# poorDuino.net
KiCad netlist of a schematic drawn in EAGLE
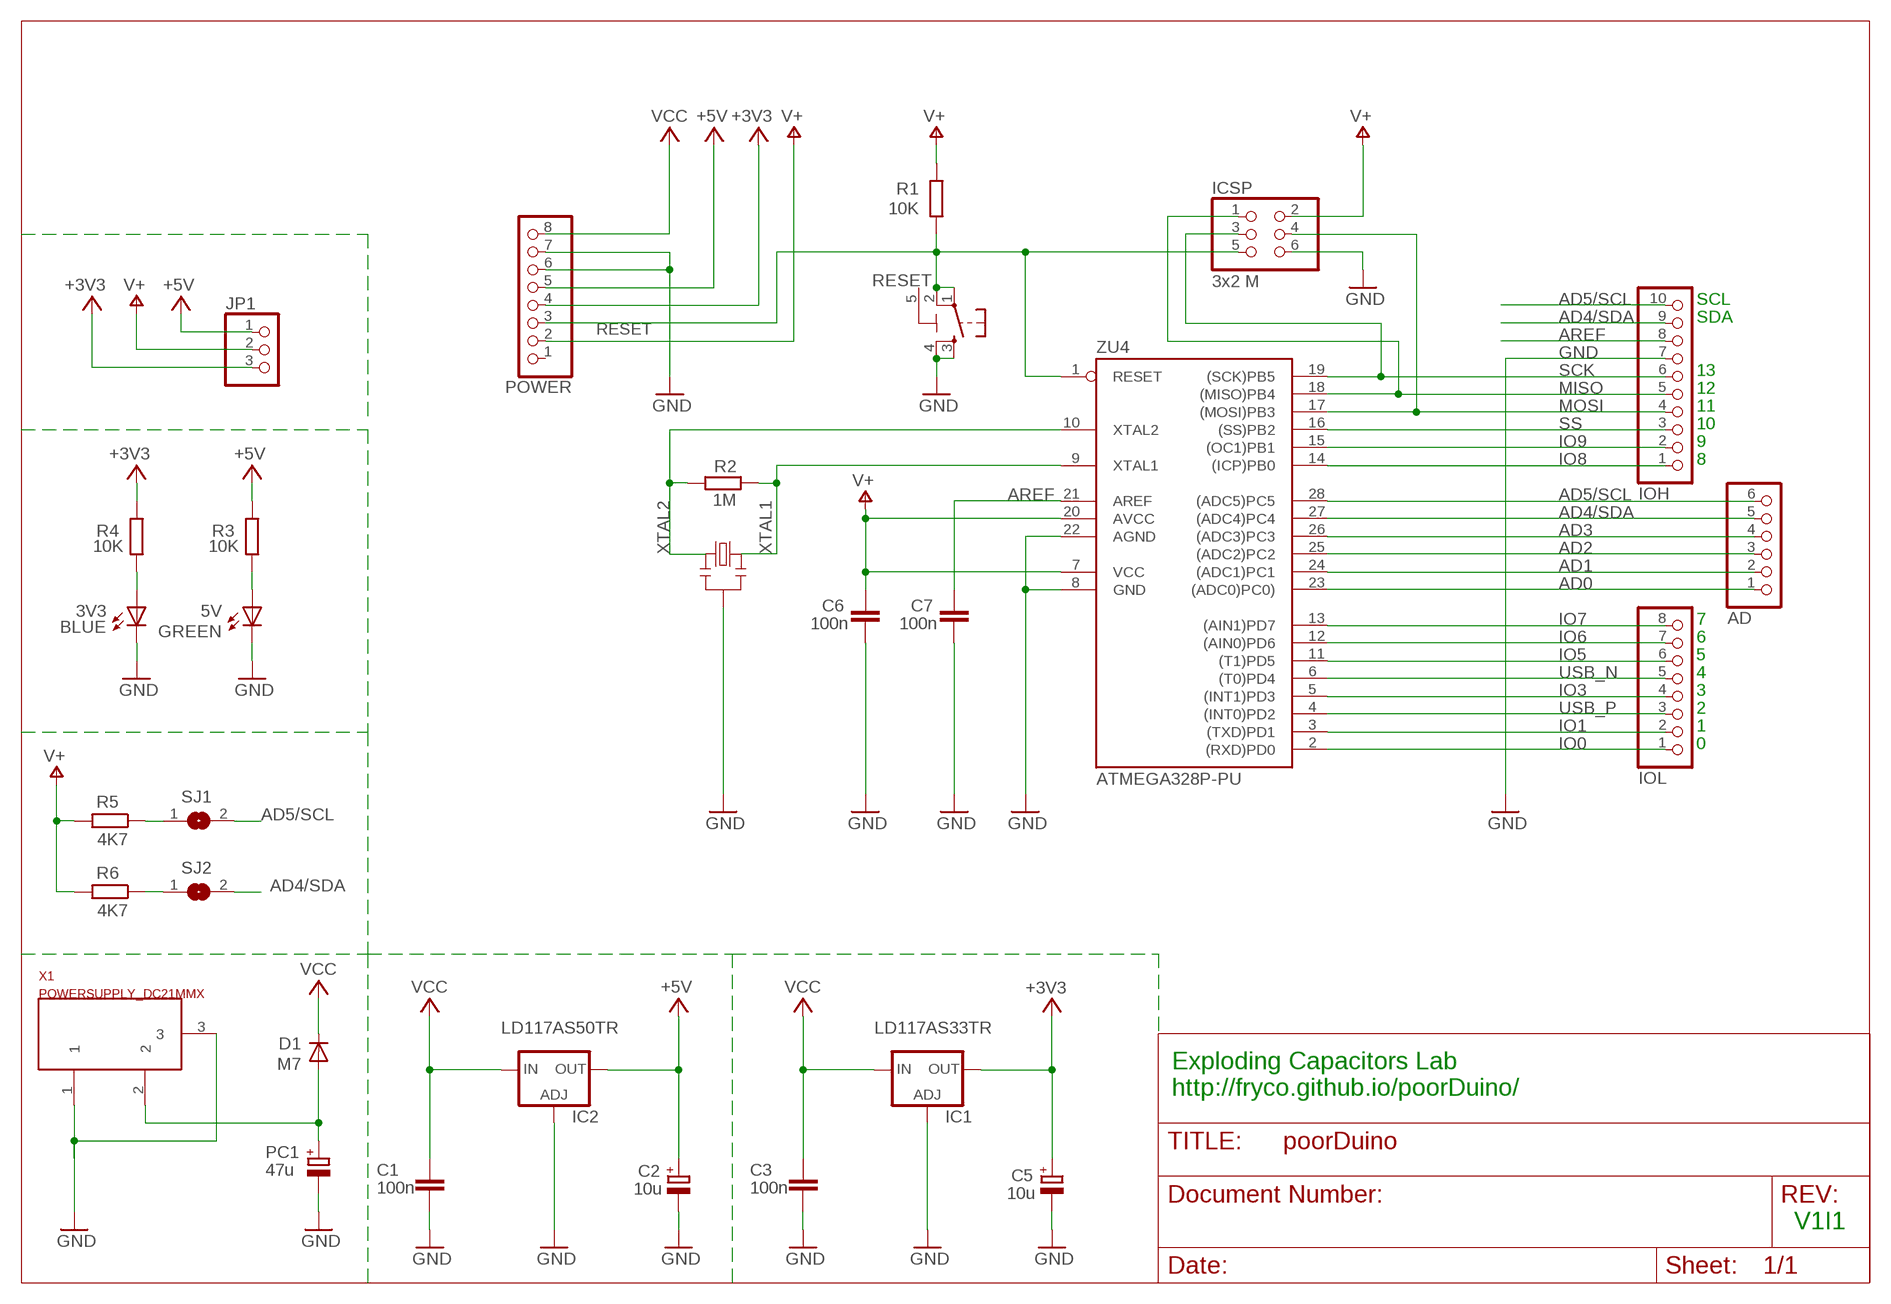
[diagram p0: schematic, sheet 1]

(export (version "E")
  (design (tool "Eeschema 10.0.6"))
  (components
    (comp (ref "3V3")
      (value "BLUE")
      (footprint "eagle-import:CHIP-LED0805")
      (libsource (lib "eagle-import") (part "LEDCHIP-LED0805"))
    )
    (comp (ref "5V")
      (value "GREEN")
      (footprint "eagle-import:CHIP-LED0805")
      (libsource (lib "eagle-import") (part "LEDCHIP-LED0805"))
    )
    (comp (ref "AD")
      (value "6x1F-H8.5")
      (footprint "eagle-import:1X06")
      (libsource (lib "eagle-import") (part "PINHD-1X6"))
    )
    (comp (ref "C1")
      (value "100n")
      (footprint "eagle-import:C0805")
      (libsource (lib "eagle-import") (part "C-EUC0805"))
    )
    (comp (ref "C2")
      (value "10u")
      (footprint "eagle-import:SMC_A")
      (libsource (lib "eagle-import") (part "CPOL-EUSMCA"))
    )
    (comp (ref "C3")
      (value "100n")
      (footprint "eagle-import:C0805")
      (libsource (lib "eagle-import") (part "C-EUC0805"))
    )
    (comp (ref "C5")
      (value "10u")
      (footprint "eagle-import:SMC_A")
      (libsource (lib "eagle-import") (part "CPOL-EUSMCA"))
    )
    (comp (ref "C6")
      (value "100n")
      (footprint "eagle-import:C0805")
      (libsource (lib "eagle-import") (part "C-EUC0805"))
    )
    (comp (ref "C7")
      (value "100n")
      (footprint "eagle-import:C0805")
      (libsource (lib "eagle-import") (part "C-EUC0805"))
    )
    (comp (ref "D1")
      (value "M7")
      (footprint "eagle-import:SMB")
      (libsource (lib "eagle-import") (part "DIODE-SMB"))
    )
    (comp (ref "IC1")
      (value "LD117AS33TR")
      (footprint "eagle-import:SOT223")
      (libsource (lib "eagle-import") (part "LD117A?S33TR"))
    )
    (comp (ref "IC2")
      (value "LD117AS50TR")
      (footprint "eagle-import:SOT223")
      (libsource (lib "eagle-import") (part "LD117A?S50TR"))
    )
    (comp (ref "ICSP")
      (value "3x2 M")
      (footprint "eagle-import:2X03")
      (libsource (lib "eagle-import") (part "PINHD-2X3"))
    )
    (comp (ref "IOH")
      (value "10x1F-H8.5")
      (footprint "eagle-import:1X10")
      (libsource (lib "eagle-import") (part "PINHD-1X10_ARD"))
    )
    (comp (ref "IOL")
      (value "8x1F-H8.5")
      (footprint "eagle-import:1X08")
      (libsource (lib "eagle-import") (part "PINHD-1X8"))
    )
    (comp (ref "JP1")
      (value "PINHD-1X3")
      (footprint "eagle-import:1X03")
      (libsource (lib "eagle-import") (part "PINHD-1X3"))
    )
    (comp (ref "PC1")
      (value "47u")
      (footprint "eagle-import:PANASONIC_D")
      (libsource (lib "eagle-import") (part "CPOL-EUD"))
    )
    (comp (ref "POWER")
      (value "8x1F-H8.5")
      (footprint "eagle-import:1X08")
      (libsource (lib "eagle-import") (part "PINHD-1X8"))
    )
    (comp (ref "R1")
      (value "10K")
      (footprint "eagle-import:R0805")
      (libsource (lib "eagle-import") (part "R-EU_R0805"))
    )
    (comp (ref "R2")
      (value "1M")
      (footprint "eagle-import:R0805")
      (libsource (lib "eagle-import") (part "R-EU_R0805"))
    )
    (comp (ref "R3")
      (value "10K")
      (footprint "eagle-import:R0805")
      (libsource (lib "eagle-import") (part "R-EU_R0805"))
    )
    (comp (ref "R4")
      (value "10K")
      (footprint "eagle-import:R0805")
      (libsource (lib "eagle-import") (part "R-EU_R0805"))
    )
    (comp (ref "R5")
      (value "4K7")
      (footprint "eagle-import:R0805")
      (libsource (lib "eagle-import") (part "R-EU_R0805"))
    )
    (comp (ref "R6")
      (value "4K7")
      (footprint "eagle-import:R0805")
      (libsource (lib "eagle-import") (part "R-EU_R0805"))
    )
    (comp (ref "RESET")
      (value "TS42031-160R-TR-7260")
      (footprint "eagle-import:TS42")
      (libsource (lib "eagle-import") (part "TS42"))
    )
    (comp (ref "SJ1") (value "SJ") (footprint "eagle-import:SJ") (libsource (lib "eagle-import") (part "SJ")))
    (comp (ref "SJ2") (value "SJ") (footprint "eagle-import:SJ") (libsource (lib "eagle-import") (part "SJ")))
    (comp (ref "X1")
      (value "POWERSUPPLY_DC21MMX")
      (footprint "eagle-import:POWERSUPPLY_DC-21MM")
      (libsource (lib "eagle-import") (part "POWERSUPPLY_DC21MMX"))
    )
    (comp (ref "Y2")
      (value "CSTCE16M0V53-R0 16MHZ")
      (footprint "eagle-import:RESONATOR")
      (libsource (lib "eagle-import") (part "RESONATORMU"))
    )
    (comp (ref "ZU4")
      (value "ATMEGA328P-PU")
      (footprint "eagle-import:DIL28-3")
      (libsource (lib "eagle-import") (part "ATMEGA328P-PU"))
    )
  )
  (nets
    (net (code "1") (name "+3V3") (class "Default")
      (node (ref "C5") (pin "+") (pinfunction "+_+") (pintype "passive"))
      (node (ref "IC1") (pin "4") (pinfunction "OUT_4") (pintype "passive"))
      (node (ref "JP1") (pin "3") (pinfunction "3_3") (pintype "passive"))
      (node (ref "POWER") (pin "4") (pinfunction "4_4") (pintype "passive"))
      (node (ref "R4") (pin "1") (pinfunction "1_1") (pintype "passive"))
    )
    (net (code "2") (name "+5V") (class "Default")
      (node (ref "C2") (pin "+") (pinfunction "+_+") (pintype "passive"))
      (node (ref "IC2") (pin "4") (pinfunction "OUT_4") (pintype "passive"))
      (node (ref "JP1") (pin "1") (pinfunction "1_1") (pintype "passive"))
      (node (ref "POWER") (pin "5") (pinfunction "5_5") (pintype "passive"))
      (node (ref "R3") (pin "1") (pinfunction "1_1") (pintype "passive"))
    )
    (net (code "3") (name "/5-GND") (class "Default")
      (node (ref "RESET") (pin "5") (pinfunction "5-GND_5") (pintype "power_in"))
    )
    (net (code "4") (name "/AD0") (class "Default")
      (node (ref "AD") (pin "1") (pinfunction "1_1") (pintype "passive"))
      (node (ref "ZU4") (pin "23") (pinfunction "(ADC0)PC0)_23") (pintype "bidirectional"))
    )
    (net (code "5") (name "/AD1") (class "Default")
      (node (ref "AD") (pin "2") (pinfunction "2_2") (pintype "passive"))
      (node (ref "ZU4") (pin "24") (pinfunction "(ADC1)PC1_24") (pintype "bidirectional"))
    )
    (net (code "6") (name "/AD2") (class "Default")
      (node (ref "AD") (pin "3") (pinfunction "3_3") (pintype "passive"))
      (node (ref "ZU4") (pin "25") (pinfunction "(ADC2)PC2_25") (pintype "bidirectional"))
    )
    (net (code "7") (name "/AD3") (class "Default")
      (node (ref "AD") (pin "4") (pinfunction "4_4") (pintype "passive"))
      (node (ref "ZU4") (pin "26") (pinfunction "(ADC3)PC3_26") (pintype "bidirectional"))
    )
    (net (code "8") (name "/AD4{slash}SDA") (class "Default")
      (node (ref "AD") (pin "5") (pinfunction "5_5") (pintype "passive"))
      (node (ref "IOH") (pin "9") (pinfunction "9_9") (pintype "passive"))
      (node (ref "SJ2") (pin "2") (pinfunction "2_2") (pintype "passive"))
      (node (ref "ZU4") (pin "27") (pinfunction "(ADC4)PC4_27") (pintype "bidirectional"))
    )
    (net (code "9") (name "/AD5{slash}SCL") (class "Default")
      (node (ref "AD") (pin "6") (pinfunction "6_6") (pintype "passive"))
      (node (ref "IOH") (pin "10") (pinfunction "10_10") (pintype "passive"))
      (node (ref "SJ1") (pin "2") (pinfunction "2_2") (pintype "passive"))
      (node (ref "ZU4") (pin "28") (pinfunction "(ADC5)PC5_28") (pintype "bidirectional"))
    )
    (net (code "10") (name "/AREF") (class "Default")
      (node (ref "C7") (pin "2") (pinfunction "2_2") (pintype "passive"))
      (node (ref "IOH") (pin "8") (pinfunction "8_8") (pintype "passive"))
      (node (ref "ZU4") (pin "21") (pinfunction "AREF_21") (pintype "passive"))
    )
    (net (code "11") (name "/IO0") (class "Default")
      (node (ref "IOL") (pin "1") (pinfunction "1_1") (pintype "passive"))
      (node (ref "ZU4") (pin "2") (pinfunction "(RXD)PD0_2") (pintype "bidirectional"))
    )
    (net (code "12") (name "/IO1") (class "Default")
      (node (ref "IOL") (pin "2") (pinfunction "2_2") (pintype "passive"))
      (node (ref "ZU4") (pin "3") (pinfunction "(TXD)PD1_3") (pintype "bidirectional"))
    )
    (net (code "13") (name "/IO3") (class "Default")
      (node (ref "IOL") (pin "4") (pinfunction "4_4") (pintype "passive"))
      (node (ref "ZU4") (pin "5") (pinfunction "(INT1)PD3_5") (pintype "bidirectional"))
    )
    (net (code "14") (name "/IO5") (class "Default")
      (node (ref "IOL") (pin "6") (pinfunction "6_6") (pintype "passive"))
      (node (ref "ZU4") (pin "11") (pinfunction "(T1)PD5_11") (pintype "bidirectional"))
    )
    (net (code "15") (name "/IO6") (class "Default")
      (node (ref "IOL") (pin "7") (pinfunction "7_7") (pintype "passive"))
      (node (ref "ZU4") (pin "12") (pinfunction "(AIN0)PD6_12") (pintype "bidirectional"))
    )
    (net (code "16") (name "/IO7") (class "Default")
      (node (ref "IOL") (pin "8") (pinfunction "8_8") (pintype "passive"))
      (node (ref "ZU4") (pin "13") (pinfunction "(AIN1)PD7_13") (pintype "bidirectional"))
    )
    (net (code "17") (name "/IO8") (class "Default")
      (node (ref "IOH") (pin "1") (pinfunction "1_1") (pintype "passive"))
      (node (ref "ZU4") (pin "14") (pinfunction "(ICP)PB0_14") (pintype "bidirectional"))
    )
    (net (code "18") (name "/IO9") (class "Default")
      (node (ref "IOH") (pin "2") (pinfunction "2_2") (pintype "passive"))
      (node (ref "ZU4") (pin "15") (pinfunction "(OC1)PB1_15") (pintype "bidirectional"))
    )
    (net (code "19") (name "/MISO") (class "Default")
      (node (ref "ICSP") (pin "1") (pinfunction "1_1") (pintype "passive"))
      (node (ref "IOH") (pin "5") (pinfunction "5_5") (pintype "passive"))
      (node (ref "ZU4") (pin "18") (pinfunction "(MISO)PB4_18") (pintype "bidirectional"))
    )
    (net (code "20") (name "/MOSI") (class "Default")
      (node (ref "ICSP") (pin "4") (pinfunction "4_4") (pintype "passive"))
      (node (ref "IOH") (pin "4") (pinfunction "4_4") (pintype "passive"))
      (node (ref "ZU4") (pin "17") (pinfunction "(MOSI)PB3_17") (pintype "bidirectional"))
    )
    (net (code "22") (name "/RESET") (class "Default")
      (node (ref "ICSP") (pin "5") (pinfunction "5_5") (pintype "passive"))
      (node (ref "POWER") (pin "3") (pinfunction "3_3") (pintype "passive"))
      (node (ref "R1") (pin "1") (pinfunction "1_1") (pintype "passive"))
      (node (ref "RESET") (pin "1") (pinfunction "1_1") (pintype "passive"))
      (node (ref "RESET") (pin "2") (pinfunction "2_2") (pintype "passive"))
      (node (ref "ZU4") (pin "1") (pinfunction "RESET_1") (pintype "input"))
    )
    (net (code "23") (name "/SCK") (class "Default")
      (node (ref "ICSP") (pin "3") (pinfunction "3_3") (pintype "passive"))
      (node (ref "IOH") (pin "6") (pinfunction "6_6") (pintype "passive"))
      (node (ref "ZU4") (pin "19") (pinfunction "(SCK)PB5_19") (pintype "bidirectional"))
    )
    (net (code "24") (name "/SS") (class "Default")
      (node (ref "IOH") (pin "3") (pinfunction "3_3") (pintype "passive"))
      (node (ref "ZU4") (pin "16") (pinfunction "(SS)PB2_16") (pintype "bidirectional"))
    )
    (net (code "25") (name "/USB_N") (class "Default")
      (node (ref "IOL") (pin "5") (pinfunction "5_5") (pintype "passive"))
      (node (ref "ZU4") (pin "6") (pinfunction "(T0)PD4_6") (pintype "bidirectional"))
    )
    (net (code "26") (name "/USB_P") (class "Default")
      (node (ref "IOL") (pin "3") (pinfunction "3_3") (pintype "passive"))
      (node (ref "ZU4") (pin "4") (pinfunction "(INT0)PD2_4") (pintype "bidirectional"))
    )
    (net (code "27") (name "/XTAL1") (class "Default")
      (node (ref "R2") (pin "1") (pinfunction "1_1") (pintype "passive"))
      (node (ref "Y2") (pin "3") (pinfunction "3_3") (pintype "passive"))
      (node (ref "ZU4") (pin "9") (pinfunction "XTAL1_9") (pintype "bidirectional"))
    )
    (net (code "28") (name "/XTAL2") (class "Default")
      (node (ref "R2") (pin "2") (pinfunction "2_2") (pintype "passive"))
      (node (ref "Y2") (pin "1") (pinfunction "1_1") (pintype "passive"))
      (node (ref "ZU4") (pin "10") (pinfunction "XTAL2_10") (pintype "bidirectional"))
    )
    (net (code "29") (name "GND") (class "Default")
      (node (ref "3V3") (pin "C") (pinfunction "C_C") (pintype "passive"))
      (node (ref "5V") (pin "C") (pinfunction "C_C") (pintype "passive"))
      (node (ref "C1") (pin "1") (pinfunction "1_1") (pintype "passive"))
      (node (ref "C2") (pin "-") (pinfunction "-_-") (pintype "passive"))
      (node (ref "C3") (pin "1") (pinfunction "1_1") (pintype "passive"))
      (node (ref "C5") (pin "-") (pinfunction "-_-") (pintype "passive"))
      (node (ref "C6") (pin "1") (pinfunction "1_1") (pintype "passive"))
      (node (ref "C7") (pin "1") (pinfunction "1_1") (pintype "passive"))
      (node (ref "IC1") (pin "1") (pinfunction "ADJ_1") (pintype "input"))
      (node (ref "IC2") (pin "1") (pinfunction "ADJ_1") (pintype "input"))
      (node (ref "ICSP") (pin "6") (pinfunction "6_6") (pintype "passive"))
      (node (ref "IOH") (pin "7") (pinfunction "7_7") (pintype "passive"))
      (node (ref "PC1") (pin "-") (pinfunction "-_-") (pintype "passive"))
      (node (ref "POWER") (pin "6") (pinfunction "6_6") (pintype "passive"))
      (node (ref "POWER") (pin "7") (pinfunction "7_7") (pintype "passive"))
      (node (ref "RESET") (pin "3") (pinfunction "3_3") (pintype "passive"))
      (node (ref "RESET") (pin "4") (pinfunction "4_4") (pintype "passive"))
      (node (ref "X1") (pin "1") (pinfunction "1_1") (pintype "power_in"))
      (node (ref "X1") (pin "3") (pinfunction "3_3") (pintype "power_in"))
      (node (ref "Y2") (pin "2") (pinfunction "2_2") (pintype "passive"))
      (node (ref "ZU4") (pin "22") (pinfunction "AGND_22") (pintype "power_in"))
      (node (ref "ZU4") (pin "8") (pinfunction "GND_8") (pintype "power_in"))
    )
    (net (code "30") (name "Net-(3V3-PadA)") (class "Default")
      (node (ref "3V3") (pin "A") (pinfunction "A_A") (pintype "passive"))
      (node (ref "R4") (pin "2") (pinfunction "2_2") (pintype "passive"))
    )
    (net (code "31") (name "Net-(5V-PadA)") (class "Default")
      (node (ref "5V") (pin "A") (pinfunction "A_A") (pintype "passive"))
      (node (ref "R3") (pin "2") (pinfunction "2_2") (pintype "passive"))
    )
    (net (code "32") (name "Net-(D1-PadA)") (class "Default")
      (node (ref "D1") (pin "A") (pinfunction "A_A") (pintype "passive"))
      (node (ref "PC1") (pin "+") (pinfunction "+_+") (pintype "passive"))
      (node (ref "X1") (pin "2") (pinfunction "2_2") (pintype "power_in"))
    )
    (net (code "33") (name "Net-(R5-Pad1)") (class "Default")
      (node (ref "R5") (pin "1") (pinfunction "1_1") (pintype "passive"))
      (node (ref "SJ1") (pin "1") (pinfunction "1_1") (pintype "passive"))
    )
    (net (code "34") (name "Net-(R6-Pad1)") (class "Default")
      (node (ref "R6") (pin "1") (pinfunction "1_1") (pintype "passive"))
      (node (ref "SJ2") (pin "1") (pinfunction "1_1") (pintype "passive"))
    )
    (net (code "35") (name "V+") (class "Default")
      (node (ref "C6") (pin "2") (pinfunction "2_2") (pintype "passive"))
      (node (ref "ICSP") (pin "2") (pinfunction "2_2") (pintype "passive"))
      (node (ref "JP1") (pin "2") (pinfunction "2_2") (pintype "passive"))
      (node (ref "POWER") (pin "2") (pinfunction "2_2") (pintype "passive"))
      (node (ref "R1") (pin "2") (pinfunction "2_2") (pintype "passive"))
      (node (ref "R5") (pin "2") (pinfunction "2_2") (pintype "passive"))
      (node (ref "R6") (pin "2") (pinfunction "2_2") (pintype "passive"))
      (node (ref "ZU4") (pin "20") (pinfunction "AVCC_20") (pintype "power_in"))
      (node (ref "ZU4") (pin "7") (pinfunction "VCC_7") (pintype "power_in"))
    )
    (net (code "36") (name "VCC") (class "Default")
      (node (ref "C1") (pin "2") (pinfunction "2_2") (pintype "passive"))
      (node (ref "C3") (pin "2") (pinfunction "2_2") (pintype "passive"))
      (node (ref "D1") (pin "C") (pinfunction "C_C") (pintype "passive"))
      (node (ref "IC1") (pin "3") (pinfunction "IN_3") (pintype "input"))
      (node (ref "IC2") (pin "3") (pinfunction "IN_3") (pintype "input"))
      (node (ref "POWER") (pin "8") (pinfunction "8_8") (pintype "passive"))
    )
    (net (code "37") (name "unconnected-(POWER-Pad1)") (class "Default")
      (node (ref "POWER") (pin "1") (pinfunction "1_1") (pintype "passive"))
    )
  )
)
